# CONNECTOR.net
KiCad netlist of a schematic drawn in Altium Designer
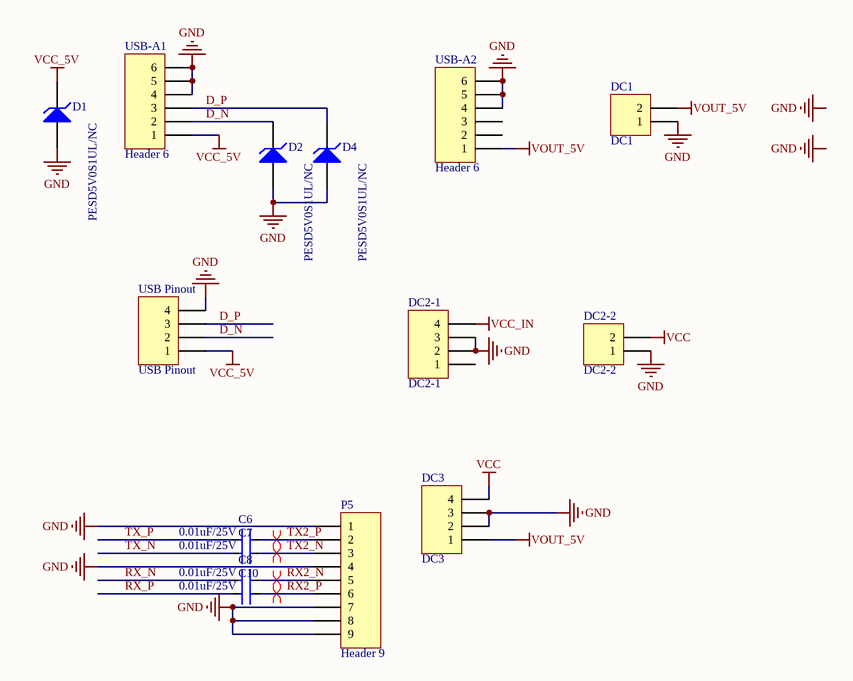
[diagram p0: CONNECTOR.SchDoc]

(export (version "E")
  (design (tool "Eeschema 10.0.6"))
  (components
    (comp (ref "C6")
      (value "0.01uF/25V")
      (footprint "0603C")
      (description "CCX85-103")
      (libsource (lib "无极性电容") (part "0.01UF"))
    )
    (comp (ref "C7")
      (value "0.01uF/25V")
      (footprint "0603C")
      (description "CCX85-103")
      (libsource (lib "无极性电容") (part "0.01UF"))
    )
    (comp (ref "C8")
      (value "0.01uF/25V")
      (footprint "0603C")
      (description "CCX85-103")
      (libsource (lib "无极性电容") (part "0.01UF"))
    )
    (comp (ref "C10")
      (value "0.01uF/25V")
      (footprint "0603C")
      (description "CCX85-103")
      (libsource (lib "无极性电容") (part "0.01UF"))
    )
    (comp (ref "D1")
      (value "PESD5V0S1UL/NC")
      (footprint "0402R")
      (description "Zener Diode")
      (fields (field (name "PUBLISHER") "Altium Limited"))
      (libsource (lib "Miscellaneous Devices") (part "D Zener"))
    )
    (comp (ref "D2")
      (value "PESD5V0S1UL/NC")
      (footprint "0402R")
      (description "Zener Diode")
      (fields (field (name "PUBLISHER") "Altium Limited"))
      (libsource (lib "Miscellaneous Devices") (part "D Zener"))
    )
    (comp (ref "D4")
      (value "PESD5V0S1UL/NC")
      (footprint "0402R")
      (description "Zener Diode")
      (fields (field (name "PUBLISHER") "Altium Limited"))
      (libsource (lib "Miscellaneous Devices") (part "D Zener"))
    )
    (comp (ref "DC1")
      (value "DC1")
      (footprint "2X2MMZ")
      (description "Header, 2-Pin")
      (fields (field (name "PUBLISHER") "Altium Limited"))
      (libsource (lib "Miscellaneous Connectors") (part "Header 2"))
    )
    (comp (ref "DC2-1")
      (value "DC2-1")
      (footprint "DC005")
      (description "Header, 4-Pin")
      (fields (field (name "PUBLISHER") "Altium Limited"))
      (libsource (lib "Miscellaneous Connectors") (part "Header 4"))
    )
    (comp (ref "DC2-2")
      (value "DC2-2")
      (footprint "2X2MMZ")
      (description "Header, 2-Pin")
      (fields (field (name "PUBLISHER") "Altium Limited"))
      (libsource (lib "Miscellaneous Connectors") (part "Header 2"))
    )
    (comp (ref "DC3")
      (value "DC3")
      (footprint "2X4MMZ")
      (description "Header, 4-Pin")
      (fields (field (name "PUBLISHER") "Altium Limited"))
      (libsource (lib "Miscellaneous Connectors") (part "Header 4"))
    )
    (comp (ref "P5")
      (value "Header 9")
      (footprint "SATA 7P")
      (description "Header, 9-Pin")
      (fields (field (name "PUBLISHER") "Altium Limited"))
      (libsource (lib "Miscellaneous Connectors") (part "Header 9"))
    )
    (comp (ref "USB Pinout")
      (value "USB Pinout")
      (footprint "sip-4l")
      (description "Header, 4-Pin")
      (fields (field (name "PUBLISHER") "Altium Limited"))
      (libsource (lib "Miscellaneous Connectors") (part "Header 4"))
    )
    (comp (ref "USB-A1")
      (value "Header 6")
      (footprint "USB-A-C")
      (description "Header, 6-Pin")
      (fields (field (name "PUBLISHER") "Altium Limited"))
      (libsource (lib "Miscellaneous Connectors") (part "Header 6"))
    )
    (comp (ref "USB-A2")
      (value "Header 6")
      (footprint "USB-A-C")
      (description "Header, 6-Pin")
      (fields (field (name "PUBLISHER") "Altium Limited"))
      (libsource (lib "Miscellaneous Connectors") (part "Header 6"))
    )
  )
  (nets
    (net (code "1") (name "/D_N") (class "Default")
      (node (ref "D2") (pin "2") (pinfunction "K_2") (pintype "passive"))
      (node (ref "USB Pinout") (pin "2") (pinfunction "2_2") (pintype "passive"))
      (node (ref "USB-A1") (pin "2") (pinfunction "2_2") (pintype "passive"))
    )
    (net (code "2") (name "/D_P") (class "Default")
      (node (ref "D4") (pin "2") (pinfunction "K_2") (pintype "passive"))
      (node (ref "USB Pinout") (pin "3") (pinfunction "3_3") (pintype "passive"))
      (node (ref "USB-A1") (pin "3") (pinfunction "3_3") (pintype "passive"))
    )
    (net (code "3") (name "/RX2_N") (class "Default")
      (node (ref "C8") (pin "2") (pinfunction "2_2") (pintype "passive"))
      (node (ref "P5") (pin "5") (pinfunction "5_5") (pintype "passive"))
    )
    (net (code "4") (name "/RX2_P") (class "Default")
      (node (ref "C10") (pin "2") (pinfunction "2_2") (pintype "passive"))
      (node (ref "P5") (pin "6") (pinfunction "6_6") (pintype "passive"))
    )
    (net (code "5") (name "/RX_N") (class "Default")
      (node (ref "C8") (pin "1") (pinfunction "1_1") (pintype "passive"))
    )
    (net (code "6") (name "/RX_P") (class "Default")
      (node (ref "C10") (pin "1") (pinfunction "1_1") (pintype "passive"))
    )
    (net (code "7") (name "/TX2_N") (class "Default")
      (node (ref "C7") (pin "2") (pinfunction "2_2") (pintype "passive"))
      (node (ref "P5") (pin "3") (pinfunction "3_3") (pintype "passive"))
    )
    (net (code "8") (name "/TX2_P") (class "Default")
      (node (ref "C6") (pin "2") (pinfunction "2_2") (pintype "passive"))
      (node (ref "P5") (pin "2") (pinfunction "2_2") (pintype "passive"))
    )
    (net (code "9") (name "/TX_N") (class "Default")
      (node (ref "C7") (pin "1") (pinfunction "1_1") (pintype "passive"))
    )
    (net (code "10") (name "/TX_P") (class "Default")
      (node (ref "C6") (pin "1") (pinfunction "1_1") (pintype "passive"))
    )
    (net (code "11") (name "GND") (class "Default")
      (node (ref "D1") (pin "1") (pinfunction "A_1") (pintype "passive"))
      (node (ref "D2") (pin "1") (pinfunction "A_1") (pintype "passive"))
      (node (ref "D4") (pin "1") (pinfunction "A_1") (pintype "passive"))
      (node (ref "DC1") (pin "1") (pinfunction "1_1") (pintype "passive"))
      (node (ref "DC2-1") (pin "2") (pinfunction "2_2") (pintype "passive"))
      (node (ref "DC2-1") (pin "3") (pinfunction "3_3") (pintype "passive"))
      (node (ref "DC2-2") (pin "1") (pinfunction "1_1") (pintype "passive"))
      (node (ref "DC3") (pin "2") (pinfunction "2_2") (pintype "passive"))
      (node (ref "DC3") (pin "3") (pinfunction "3_3") (pintype "passive"))
      (node (ref "P5") (pin "1") (pinfunction "1_1") (pintype "passive"))
      (node (ref "P5") (pin "4") (pinfunction "4_4") (pintype "passive"))
      (node (ref "P5") (pin "7") (pinfunction "7_7") (pintype "passive"))
      (node (ref "P5") (pin "8") (pinfunction "8_8") (pintype "passive"))
      (node (ref "P5") (pin "9") (pinfunction "9_9") (pintype "passive"))
      (node (ref "USB Pinout") (pin "4") (pinfunction "4_4") (pintype "passive"))
      (node (ref "USB-A1") (pin "4") (pinfunction "4_4") (pintype "passive"))
      (node (ref "USB-A1") (pin "5") (pinfunction "5_5") (pintype "passive"))
      (node (ref "USB-A1") (pin "6") (pinfunction "6_6") (pintype "passive"))
      (node (ref "USB-A2") (pin "4") (pinfunction "4_4") (pintype "passive"))
      (node (ref "USB-A2") (pin "5") (pinfunction "5_5") (pintype "passive"))
      (node (ref "USB-A2") (pin "6") (pinfunction "6_6") (pintype "passive"))
    )
    (net (code "12") (name "VCC") (class "Default")
      (node (ref "DC2-2") (pin "2") (pinfunction "2_2") (pintype "passive"))
      (node (ref "DC3") (pin "4") (pinfunction "4_4") (pintype "passive"))
    )
    (net (code "13") (name "VCC_5V") (class "Default")
      (node (ref "D1") (pin "2") (pinfunction "K_2") (pintype "passive"))
      (node (ref "USB Pinout") (pin "1") (pinfunction "1_1") (pintype "passive"))
      (node (ref "USB-A1") (pin "1") (pinfunction "1_1") (pintype "passive"))
    )
    (net (code "14") (name "VCC_IN") (class "Default")
      (node (ref "DC2-1") (pin "4") (pinfunction "4_4") (pintype "passive"))
    )
    (net (code "15") (name "VOUT_5V") (class "Default")
      (node (ref "DC1") (pin "2") (pinfunction "2_2") (pintype "passive"))
      (node (ref "DC3") (pin "1") (pinfunction "1_1") (pintype "passive"))
      (node (ref "USB-A2") (pin "1") (pinfunction "1_1") (pintype "passive"))
    )
    (net (code "16") (name "unconnected-(DC2-1-Pad1)") (class "Default")
      (node (ref "DC2-1") (pin "1") (pinfunction "1_1") (pintype "passive"))
    )
    (net (code "17") (name "unconnected-(USB-A2-Pad2)") (class "Default")
      (node (ref "USB-A2") (pin "2") (pinfunction "2_2") (pintype "passive"))
    )
    (net (code "18") (name "unconnected-(USB-A2-Pad3)") (class "Default")
      (node (ref "USB-A2") (pin "3") (pinfunction "3_3") (pintype "passive"))
    )
  )
)
